# main-board.net
KiCad netlist of a schematic drawn in EAGLE
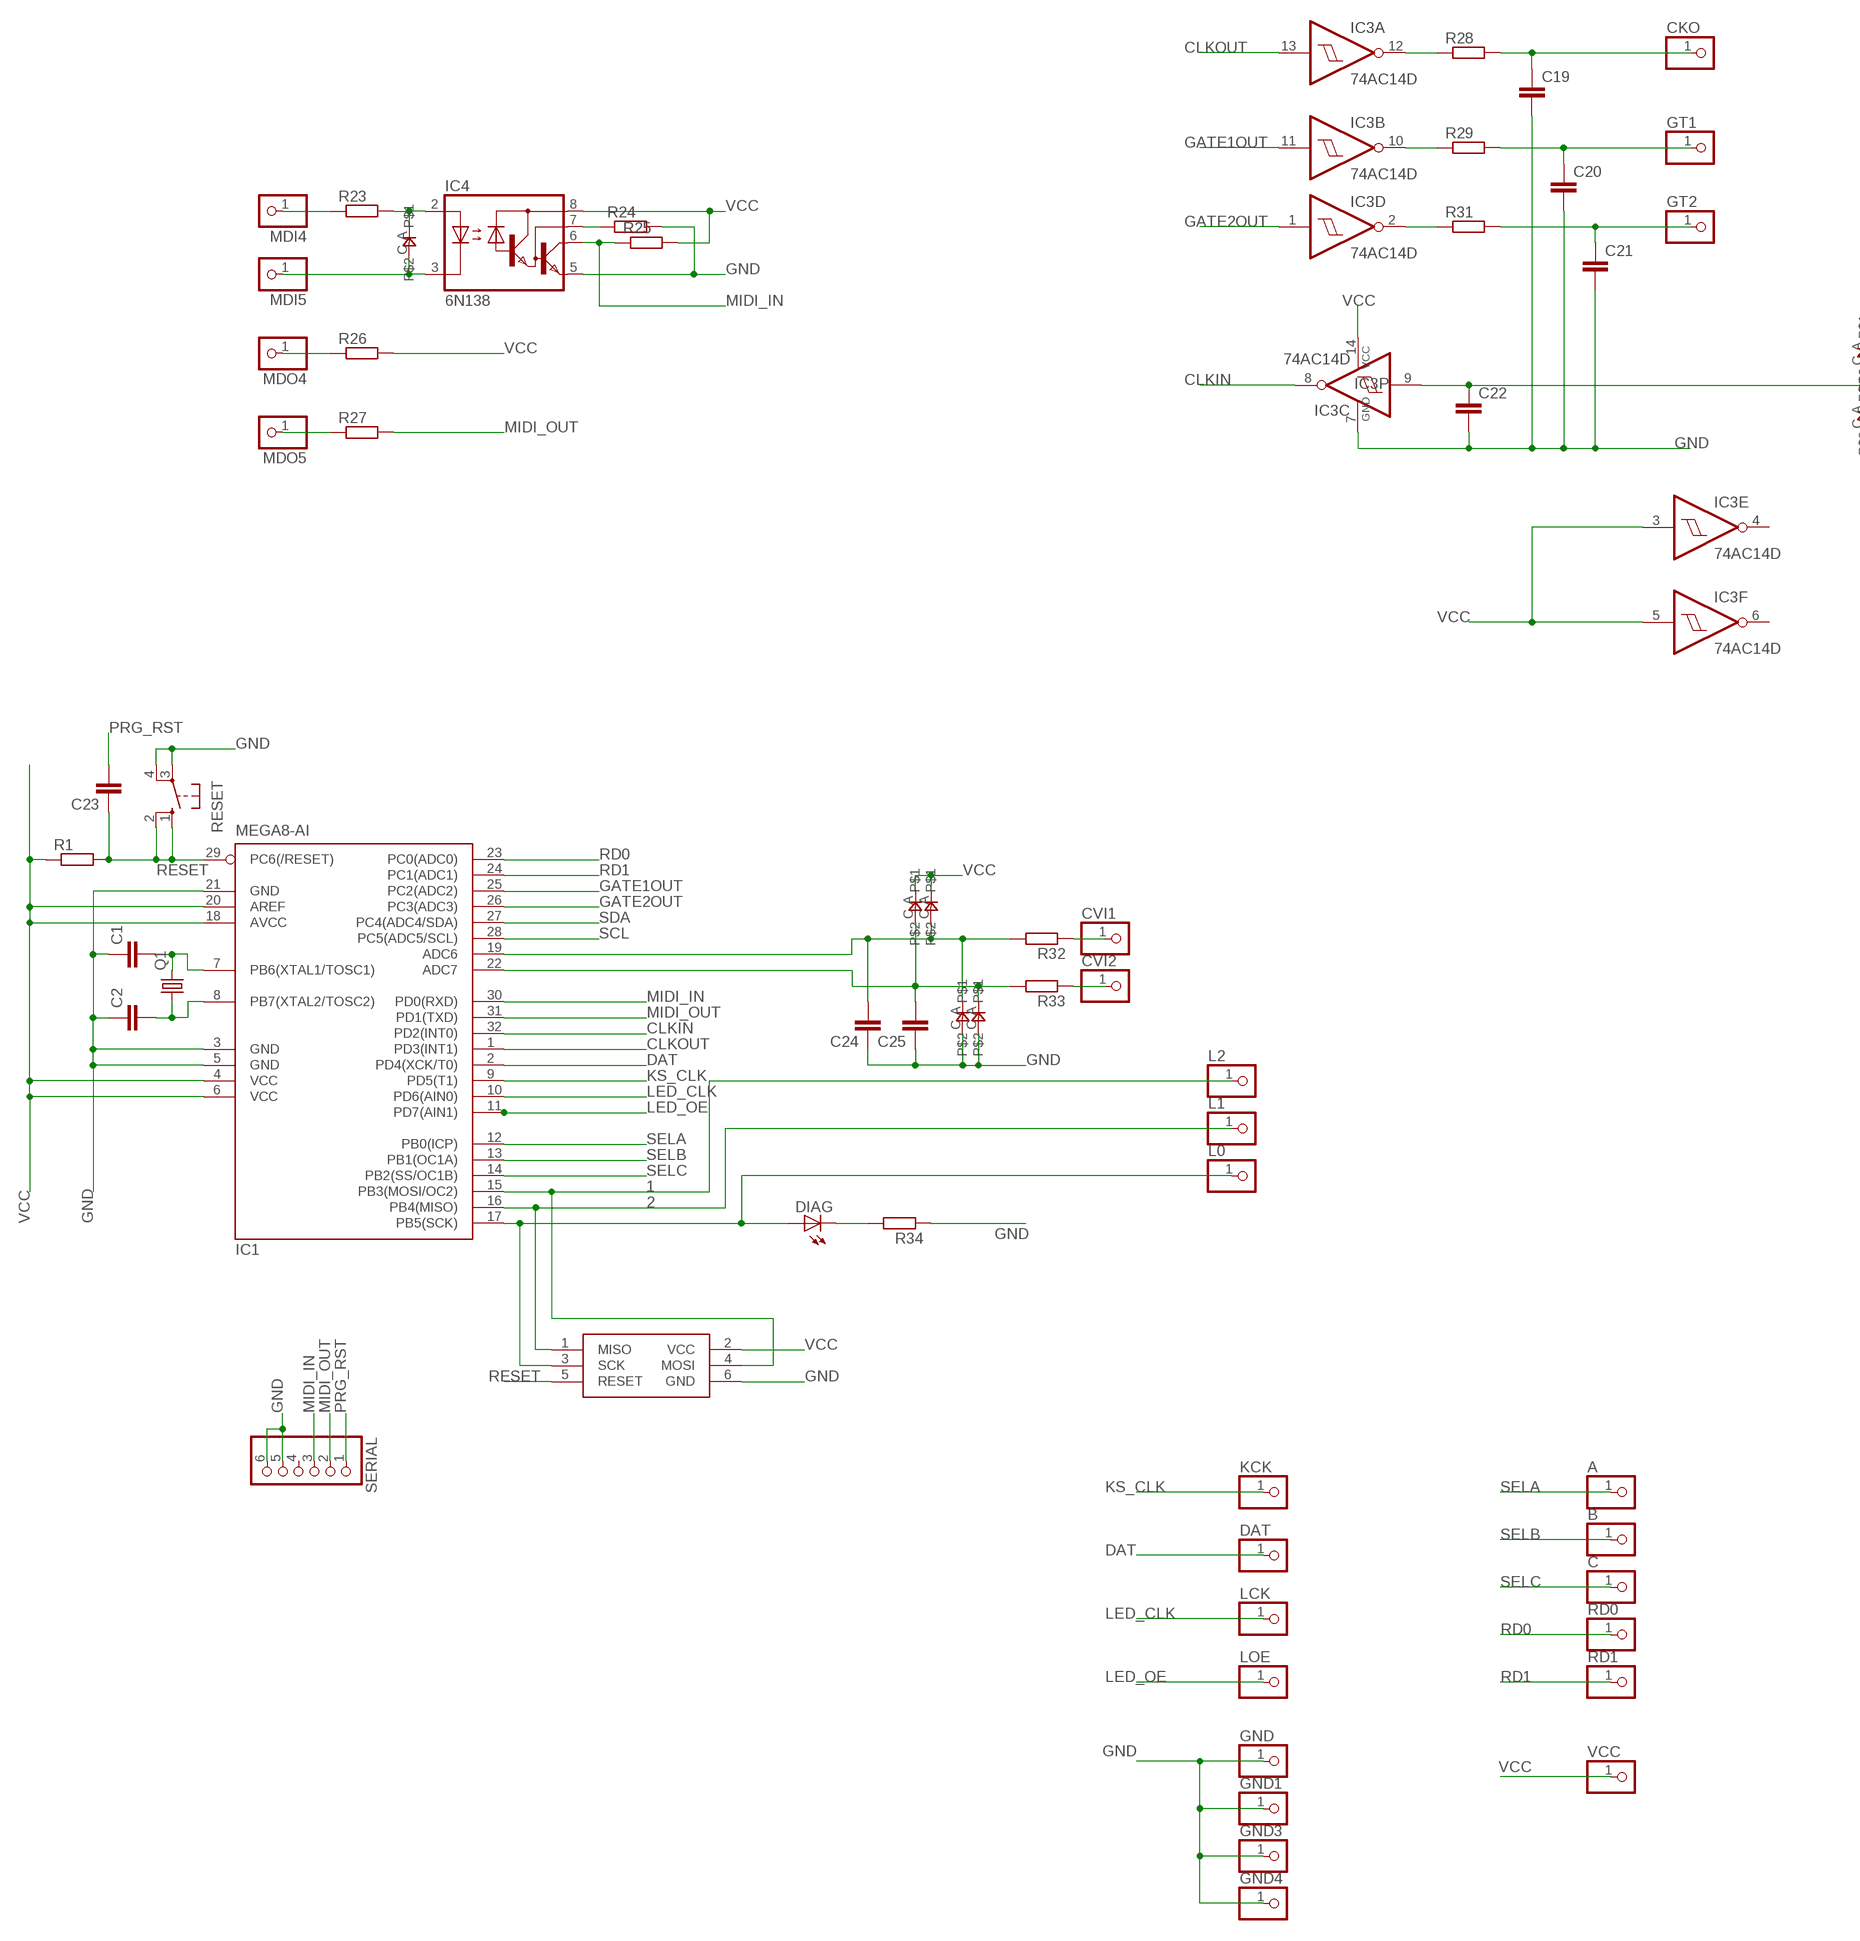
[diagram p0: schematic, sheet 1, part 1 of 2]
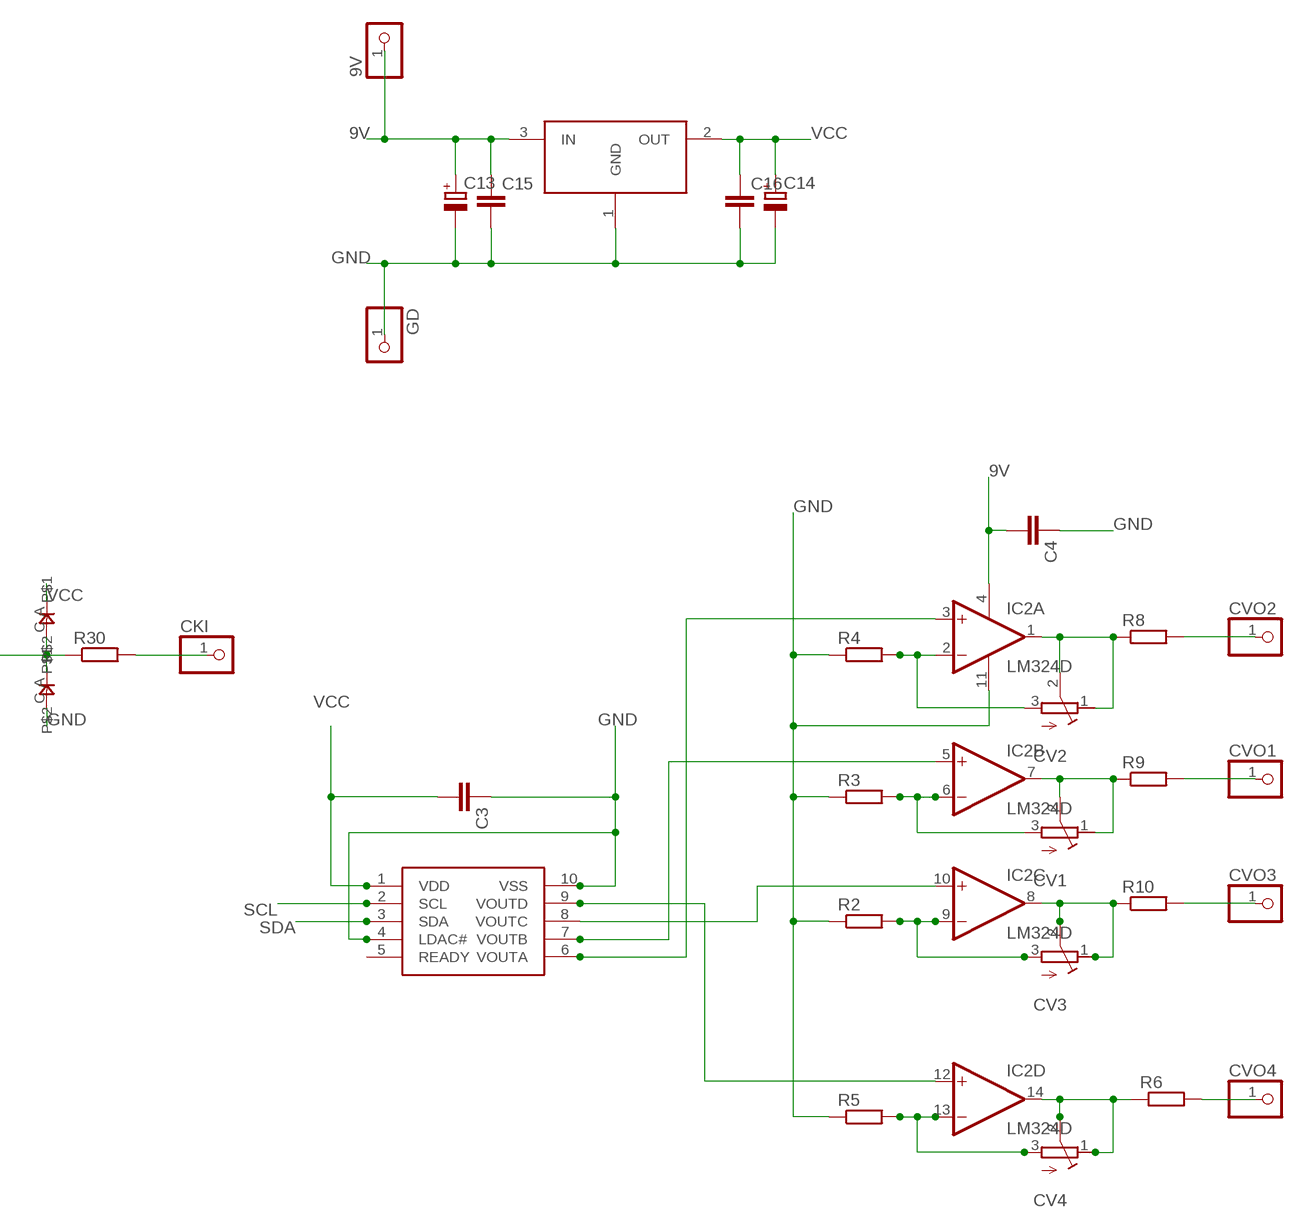
[diagram p1: schematic, sheet 1, part 2 of 2]

(export (version "E")
  (design (tool "Eeschema 10.0.6"))
  (components
    (comp (ref "9V")
      (value "PINHD-1X1")
      (footprint "eagle-import:1X01")
      (libsource (lib "eagle-import") (part "PINHD-1X1"))
    )
    (comp (ref "A")
      (value "PINHD-1X1")
      (footprint "eagle-import:1X01")
      (libsource (lib "eagle-import") (part "PINHD-1X1"))
    )
    (comp (ref "B")
      (value "PINHD-1X1")
      (footprint "eagle-import:1X01")
      (libsource (lib "eagle-import") (part "PINHD-1X1"))
    )
    (comp (ref "C")
      (value "PINHD-1X1")
      (footprint "eagle-import:1X01")
      (libsource (lib "eagle-import") (part "PINHD-1X1"))
    )
    (comp (ref "C1")
      (value "C-EUC0805")
      (footprint "eagle-import:C0805")
      (libsource (lib "eagle-import") (part "C-EUC0805"))
    )
    (comp (ref "C2")
      (value "C-EUC0805")
      (footprint "eagle-import:C0805")
      (libsource (lib "eagle-import") (part "C-EUC0805"))
    )
    (comp (ref "C3")
      (value "C-EUC0805")
      (footprint "eagle-import:C0805")
      (libsource (lib "eagle-import") (part "C-EUC0805"))
    )
    (comp (ref "C4")
      (value "C-EUC0805")
      (footprint "eagle-import:C0805")
      (libsource (lib "eagle-import") (part "C-EUC0805"))
    )
    (comp (ref "C13")
      (value "CPOL-EUE2-5")
      (footprint "eagle-import:E2-5")
      (libsource (lib "eagle-import") (part "CPOL-EUE2-5"))
    )
    (comp (ref "C14")
      (value "CPOL-EUE2-5")
      (footprint "eagle-import:E2-5")
      (libsource (lib "eagle-import") (part "CPOL-EUE2-5"))
    )
    (comp (ref "C15")
      (value "C-EUC0805")
      (footprint "eagle-import:C0805")
      (libsource (lib "eagle-import") (part "C-EUC0805"))
    )
    (comp (ref "C16")
      (value "C-EUC0805")
      (footprint "eagle-import:C0805")
      (libsource (lib "eagle-import") (part "C-EUC0805"))
    )
    (comp (ref "C19")
      (value "C-EUC0805")
      (footprint "eagle-import:C0805")
      (libsource (lib "eagle-import") (part "C-EUC0805"))
    )
    (comp (ref "C20")
      (value "C-EUC0805")
      (footprint "eagle-import:C0805")
      (libsource (lib "eagle-import") (part "C-EUC0805"))
    )
    (comp (ref "C21")
      (value "C-EUC0805")
      (footprint "eagle-import:C0805")
      (libsource (lib "eagle-import") (part "C-EUC0805"))
    )
    (comp (ref "C22")
      (value "C-EUC0805")
      (footprint "eagle-import:C0805")
      (libsource (lib "eagle-import") (part "C-EUC0805"))
    )
    (comp (ref "C23")
      (value "C-EUC0805")
      (footprint "eagle-import:C0805")
      (libsource (lib "eagle-import") (part "C-EUC0805"))
    )
    (comp (ref "C24")
      (value "C-EUC0805")
      (footprint "eagle-import:C0805")
      (libsource (lib "eagle-import") (part "C-EUC0805"))
    )
    (comp (ref "C25")
      (value "C-EUC0805")
      (footprint "eagle-import:C0805")
      (libsource (lib "eagle-import") (part "C-EUC0805"))
    )
    (comp (ref "CKI")
      (value "PINHD-1X1")
      (footprint "eagle-import:1X01")
      (libsource (lib "eagle-import") (part "PINHD-1X1"))
    )
    (comp (ref "CKO")
      (value "PINHD-1X1")
      (footprint "eagle-import:1X01")
      (libsource (lib "eagle-import") (part "PINHD-1X1"))
    )
    (comp (ref "CV1")
      (value "R-TRIMM3006P")
      (footprint "eagle-import:RTRIM3006P")
      (libsource (lib "eagle-import") (part "R-TRIMM3006P"))
    )
    (comp (ref "CV2")
      (value "R-TRIMM3006P")
      (footprint "eagle-import:RTRIM3006P")
      (libsource (lib "eagle-import") (part "R-TRIMM3006P"))
    )
    (comp (ref "CV3")
      (value "R-TRIMM3006P")
      (footprint "eagle-import:RTRIM3006P")
      (libsource (lib "eagle-import") (part "R-TRIMM3006P"))
    )
    (comp (ref "CV4")
      (value "R-TRIMM3006P")
      (footprint "eagle-import:RTRIM3006P")
      (libsource (lib "eagle-import") (part "R-TRIMM3006P"))
    )
    (comp (ref "CVI1")
      (value "PINHD-1X1")
      (footprint "eagle-import:1X01")
      (libsource (lib "eagle-import") (part "PINHD-1X1"))
    )
    (comp (ref "CVI2")
      (value "PINHD-1X1")
      (footprint "eagle-import:1X01")
      (libsource (lib "eagle-import") (part "PINHD-1X1"))
    )
    (comp (ref "CVO1")
      (value "PINHD-1X1")
      (footprint "eagle-import:1X01")
      (libsource (lib "eagle-import") (part "PINHD-1X1"))
    )
    (comp (ref "CVO2")
      (value "PINHD-1X1")
      (footprint "eagle-import:1X01")
      (libsource (lib "eagle-import") (part "PINHD-1X1"))
    )
    (comp (ref "CVO3")
      (value "PINHD-1X1")
      (footprint "eagle-import:1X01")
      (libsource (lib "eagle-import") (part "PINHD-1X1"))
    )
    (comp (ref "CVO4")
      (value "PINHD-1X1")
      (footprint "eagle-import:1X01")
      (libsource (lib "eagle-import") (part "PINHD-1X1"))
    )
    (comp (ref "D1")
      (value "0805DIODE")
      (footprint "eagle-import:0805DIODE")
      (libsource (lib "eagle-import") (part "0805DIODE"))
    )
    (comp (ref "D2")
      (value "0805DIODE")
      (footprint "eagle-import:0805DIODE")
      (libsource (lib "eagle-import") (part "0805DIODE"))
    )
    (comp (ref "D3")
      (value "0805DIODE")
      (footprint "eagle-import:0805DIODE")
      (libsource (lib "eagle-import") (part "0805DIODE"))
    )
    (comp (ref "D4")
      (value "0805DIODE")
      (footprint "eagle-import:0805DIODE")
      (libsource (lib "eagle-import") (part "0805DIODE"))
    )
    (comp (ref "D5")
      (value "0805DIODE")
      (footprint "eagle-import:0805DIODE")
      (libsource (lib "eagle-import") (part "0805DIODE"))
    )
    (comp (ref "D6")
      (value "0805DIODE")
      (footprint "eagle-import:0805DIODE")
      (libsource (lib "eagle-import") (part "0805DIODE"))
    )
    (comp (ref "D7")
      (value "0805DIODE")
      (footprint "eagle-import:0805DIODE")
      (libsource (lib "eagle-import") (part "0805DIODE"))
    )
    (comp (ref "DAT")
      (value "PINHD-1X1")
      (footprint "eagle-import:1X01")
      (libsource (lib "eagle-import") (part "PINHD-1X1"))
    )
    (comp (ref "DIAG")
      (value "LED3MM")
      (footprint "eagle-import:LED3MM")
      (libsource (lib "eagle-import") (part "LED3MM"))
    )
    (comp (ref "GD")
      (value "PINHD-1X1")
      (footprint "eagle-import:1X01")
      (libsource (lib "eagle-import") (part "PINHD-1X1"))
    )
    (comp (ref "GND")
      (value "PINHD-1X1")
      (footprint "eagle-import:1X01")
      (libsource (lib "eagle-import") (part "PINHD-1X1"))
    )
    (comp (ref "GND1")
      (value "PINHD-1X1")
      (footprint "eagle-import:1X01")
      (libsource (lib "eagle-import") (part "PINHD-1X1"))
    )
    (comp (ref "GND3")
      (value "PINHD-1X1")
      (footprint "eagle-import:1X01")
      (libsource (lib "eagle-import") (part "PINHD-1X1"))
    )
    (comp (ref "GND4")
      (value "PINHD-1X1")
      (footprint "eagle-import:1X01")
      (libsource (lib "eagle-import") (part "PINHD-1X1"))
    )
    (comp (ref "GT1")
      (value "PINHD-1X1")
      (footprint "eagle-import:1X01")
      (libsource (lib "eagle-import") (part "PINHD-1X1"))
    )
    (comp (ref "GT2")
      (value "PINHD-1X1")
      (footprint "eagle-import:1X01")
      (libsource (lib "eagle-import") (part "PINHD-1X1"))
    )
    (comp (ref "IC1")
      (value "MEGA8-AI")
      (footprint "eagle-import:TQFP32-08")
      (fields (field (name "MPN") "ATMEGA8-16AU"))
      (libsource (lib "eagle-import") (part "MEGA8-AI"))
    )
    (comp (ref "IC2")
      (value "LM324D")
      (footprint "eagle-import:SO14")
      (libsource (lib "eagle-import") (part "LM324D"))
    )
    (comp (ref "IC3")
      (value "74AC14D")
      (footprint "eagle-import:SO14")
      (libsource (lib "eagle-import") (part "7414DAC"))
    )
    (comp (ref "IC4")
      (value "6N138")
      (footprint "eagle-import:DIL08")
      (fields (field (name "MF") "VISHAY/TELEFUNKEN"))
      (libsource (lib "eagle-import") (part "6N138"))
    )
    (comp (ref "IC5")
      (value "MCP4728_QUAD_DAC")
      (footprint "eagle-import:MSOP10")
      (libsource (lib "eagle-import") (part "MCP4728_QUAD_DAC"))
    )
    (comp (ref "ICSP")
      (value "TAG_CONN_AVR")
      (footprint "eagle-import:TC2030-MCP-NL")
      (libsource (lib "eagle-import") (part "TAG_CONN_AVR"))
    )
    (comp (ref "KCK")
      (value "PINHD-1X1")
      (footprint "eagle-import:1X01")
      (libsource (lib "eagle-import") (part "PINHD-1X1"))
    )
    (comp (ref "L0")
      (value "PINHD-1X1")
      (footprint "eagle-import:1X01")
      (libsource (lib "eagle-import") (part "PINHD-1X1"))
    )
    (comp (ref "L1")
      (value "PINHD-1X1")
      (footprint "eagle-import:1X01")
      (libsource (lib "eagle-import") (part "PINHD-1X1"))
    )
    (comp (ref "L2")
      (value "PINHD-1X1")
      (footprint "eagle-import:1X01")
      (libsource (lib "eagle-import") (part "PINHD-1X1"))
    )
    (comp (ref "LCK")
      (value "PINHD-1X1")
      (footprint "eagle-import:1X01")
      (libsource (lib "eagle-import") (part "PINHD-1X1"))
    )
    (comp (ref "LOE")
      (value "PINHD-1X1")
      (footprint "eagle-import:1X01")
      (libsource (lib "eagle-import") (part "PINHD-1X1"))
    )
    (comp (ref "MDI4")
      (value "PINHD-1X1")
      (footprint "eagle-import:1X01")
      (libsource (lib "eagle-import") (part "PINHD-1X1"))
    )
    (comp (ref "MDI5")
      (value "PINHD-1X1")
      (footprint "eagle-import:1X01")
      (libsource (lib "eagle-import") (part "PINHD-1X1"))
    )
    (comp (ref "MDO4")
      (value "PINHD-1X1")
      (footprint "eagle-import:1X01")
      (libsource (lib "eagle-import") (part "PINHD-1X1"))
    )
    (comp (ref "MDO5")
      (value "PINHD-1X1")
      (footprint "eagle-import:1X01")
      (libsource (lib "eagle-import") (part "PINHD-1X1"))
    )
    (comp (ref "Q1")
      (value "CRYSTALHC49S")
      (footprint "eagle-import:HC49_S")
      (libsource (lib "eagle-import") (part "CRYSTALHC49S"))
    )
    (comp (ref "R1")
      (value "R-EU_R0805")
      (footprint "eagle-import:R0805")
      (libsource (lib "eagle-import") (part "R-EU_R0805"))
    )
    (comp (ref "R2")
      (value "R-EU_R0805")
      (footprint "eagle-import:R0805")
      (libsource (lib "eagle-import") (part "R-EU_R0805"))
    )
    (comp (ref "R3")
      (value "R-EU_R0805")
      (footprint "eagle-import:R0805")
      (libsource (lib "eagle-import") (part "R-EU_R0805"))
    )
    (comp (ref "R4")
      (value "R-EU_R0805")
      (footprint "eagle-import:R0805")
      (libsource (lib "eagle-import") (part "R-EU_R0805"))
    )
    (comp (ref "R5")
      (value "R-EU_R0805")
      (footprint "eagle-import:R0805")
      (libsource (lib "eagle-import") (part "R-EU_R0805"))
    )
    (comp (ref "R6")
      (value "R-EU_R0805")
      (footprint "eagle-import:R0805")
      (libsource (lib "eagle-import") (part "R-EU_R0805"))
    )
    (comp (ref "R8")
      (value "R-EU_R0805")
      (footprint "eagle-import:R0805")
      (libsource (lib "eagle-import") (part "R-EU_R0805"))
    )
    (comp (ref "R9")
      (value "R-EU_R0805")
      (footprint "eagle-import:R0805")
      (libsource (lib "eagle-import") (part "R-EU_R0805"))
    )
    (comp (ref "R10")
      (value "R-EU_R0805")
      (footprint "eagle-import:R0805")
      (libsource (lib "eagle-import") (part "R-EU_R0805"))
    )
    (comp (ref "R23")
      (value "R-EU_R0805")
      (footprint "eagle-import:R0805")
      (libsource (lib "eagle-import") (part "R-EU_R0805"))
    )
    (comp (ref "R24")
      (value "R-EU_R0805")
      (footprint "eagle-import:R0805")
      (libsource (lib "eagle-import") (part "R-EU_R0805"))
    )
    (comp (ref "R25")
      (value "R-EU_R0805")
      (footprint "eagle-import:R0805")
      (libsource (lib "eagle-import") (part "R-EU_R0805"))
    )
    (comp (ref "R26")
      (value "R-EU_R0805")
      (footprint "eagle-import:R0805")
      (libsource (lib "eagle-import") (part "R-EU_R0805"))
    )
    (comp (ref "R27")
      (value "R-EU_R0805")
      (footprint "eagle-import:R0805")
      (libsource (lib "eagle-import") (part "R-EU_R0805"))
    )
    (comp (ref "R28")
      (value "R-EU_R0805")
      (footprint "eagle-import:R0805")
      (libsource (lib "eagle-import") (part "R-EU_R0805"))
    )
    (comp (ref "R29")
      (value "R-EU_R0805")
      (footprint "eagle-import:R0805")
      (libsource (lib "eagle-import") (part "R-EU_R0805"))
    )
    (comp (ref "R30")
      (value "R-EU_R0805")
      (footprint "eagle-import:R0805")
      (libsource (lib "eagle-import") (part "R-EU_R0805"))
    )
    (comp (ref "R31")
      (value "R-EU_R0805")
      (footprint "eagle-import:R0805")
      (libsource (lib "eagle-import") (part "R-EU_R0805"))
    )
    (comp (ref "R32")
      (value "R-EU_R0805")
      (footprint "eagle-import:R0805")
      (libsource (lib "eagle-import") (part "R-EU_R0805"))
    )
    (comp (ref "R33")
      (value "R-EU_R0805")
      (footprint "eagle-import:R0805")
      (libsource (lib "eagle-import") (part "R-EU_R0805"))
    )
    (comp (ref "R34")
      (value "R-EU_R0805")
      (footprint "eagle-import:R0805")
      (libsource (lib "eagle-import") (part "R-EU_R0805"))
    )
    (comp (ref "RD0")
      (value "PINHD-1X1")
      (footprint "eagle-import:1X01")
      (libsource (lib "eagle-import") (part "PINHD-1X1"))
    )
    (comp (ref "RD1")
      (value "PINHD-1X1")
      (footprint "eagle-import:1X01")
      (libsource (lib "eagle-import") (part "PINHD-1X1"))
    )
    (comp (ref "REG1")
      (value "LD1086")
      (footprint "eagle-import:DPACK")
      (libsource (lib "eagle-import") (part "LD1086"))
    )
    (comp (ref "RESET")
      (value "10-XX")
      (footprint "eagle-import:B3F-10XX")
      (fields (field (name "MPN") "B3F-1000"))
      (libsource (lib "eagle-import") (part "10-XX"))
    )
    (comp (ref "SERIAL")
      (value "PINHD-1X6")
      (footprint "eagle-import:1X06")
      (libsource (lib "eagle-import") (part "PINHD-1X6"))
    )
    (comp (ref "VCC")
      (value "PINHD-1X1")
      (footprint "eagle-import:1X01")
      (libsource (lib "eagle-import") (part "PINHD-1X1"))
    )
  )
  (nets
    (net (code "1") (name "/1") (class "Default")
      (node (ref "IC1") (pin "15") (pinfunction "PB3(MOSI/OC2)_15") (pintype "bidirectional"))
      (node (ref "ICSP") (pin "4") (pinfunction "MOSI_4") (pintype "bidirectional"))
      (node (ref "L2") (pin "1") (pinfunction "1_1") (pintype "passive"))
    )
    (net (code "2") (name "/2") (class "Default")
      (node (ref "IC1") (pin "16") (pinfunction "PB4(MISO)_16") (pintype "bidirectional"))
      (node (ref "ICSP") (pin "1") (pinfunction "MISO_1") (pintype "bidirectional"))
      (node (ref "L1") (pin "1") (pinfunction "1_1") (pintype "passive"))
    )
    (net (code "3") (name "/9V") (class "Default")
      (node (ref "9V") (pin "1") (pinfunction "1_1") (pintype "passive"))
      (node (ref "C13") (pin "+") (pinfunction "+_+") (pintype "passive"))
      (node (ref "C15") (pin "1") (pinfunction "1_1") (pintype "passive"))
      (node (ref "C4") (pin "2") (pinfunction "2_2") (pintype "passive"))
      (node (ref "IC2") (pin "4") (pinfunction "V+_4") (pintype "power_in"))
      (node (ref "REG1") (pin "3") (pinfunction "IN_3") (pintype "bidirectional"))
    )
    (net (code "4") (name "/CLKIN") (class "Default")
      (node (ref "IC1") (pin "32") (pinfunction "PD2(INT0)_32") (pintype "bidirectional"))
      (node (ref "IC3") (pin "8") (pinfunction "O_8") (pintype "output"))
    )
    (net (code "5") (name "/CLKOUT") (class "Default")
      (node (ref "IC1") (pin "1") (pinfunction "PD3(INT1)_1") (pintype "bidirectional"))
      (node (ref "IC3") (pin "13") (pinfunction "I_13") (pintype "input"))
    )
    (net (code "6") (name "/DAT") (class "Default")
      (node (ref "DAT") (pin "1") (pinfunction "1_1") (pintype "passive"))
      (node (ref "IC1") (pin "2") (pinfunction "PD4(XCK/T0)_2") (pintype "bidirectional"))
    )
    (net (code "7") (name "/GATE1OUT") (class "Default")
      (node (ref "IC1") (pin "25") (pinfunction "PC2(ADC2)_25") (pintype "bidirectional"))
      (node (ref "IC3") (pin "11") (pinfunction "I_11") (pintype "input"))
    )
    (net (code "8") (name "/GATE2OUT") (class "Default")
      (node (ref "IC1") (pin "26") (pinfunction "PC3(ADC3)_26") (pintype "bidirectional"))
      (node (ref "IC3") (pin "1") (pinfunction "I_1") (pintype "input"))
    )
    (net (code "9") (name "/GND") (class "Default")
      (node (ref "C1") (pin "1") (pinfunction "1_1") (pintype "passive"))
      (node (ref "C13") (pin "-") (pinfunction "-_-") (pintype "passive"))
      (node (ref "C14") (pin "-") (pinfunction "-_-") (pintype "passive"))
      (node (ref "C15") (pin "2") (pinfunction "2_2") (pintype "passive"))
      (node (ref "C16") (pin "2") (pinfunction "2_2") (pintype "passive"))
      (node (ref "C19") (pin "2") (pinfunction "2_2") (pintype "passive"))
      (node (ref "C2") (pin "1") (pinfunction "1_1") (pintype "passive"))
      (node (ref "C20") (pin "2") (pinfunction "2_2") (pintype "passive"))
      (node (ref "C21") (pin "2") (pinfunction "2_2") (pintype "passive"))
      (node (ref "C22") (pin "2") (pinfunction "2_2") (pintype "passive"))
      (node (ref "C24") (pin "1") (pinfunction "1_1") (pintype "passive"))
      (node (ref "C25") (pin "1") (pinfunction "1_1") (pintype "passive"))
      (node (ref "C3") (pin "1") (pinfunction "1_1") (pintype "passive"))
      (node (ref "C4") (pin "1") (pinfunction "1_1") (pintype "passive"))
      (node (ref "D2") (pin "C") (pinfunction "P$1_C") (pintype "bidirectional"))
      (node (ref "D4") (pin "C") (pinfunction "P$1_C") (pintype "bidirectional"))
      (node (ref "D6") (pin "C") (pinfunction "P$1_C") (pintype "bidirectional"))
      (node (ref "GD") (pin "1") (pinfunction "1_1") (pintype "passive"))
      (node (ref "GND") (pin "1") (pinfunction "1_1") (pintype "passive"))
      (node (ref "GND1") (pin "1") (pinfunction "1_1") (pintype "passive"))
      (node (ref "GND3") (pin "1") (pinfunction "1_1") (pintype "passive"))
      (node (ref "GND4") (pin "1") (pinfunction "1_1") (pintype "passive"))
      (node (ref "IC1") (pin "21") (pinfunction "GND_21") (pintype "power_in"))
      (node (ref "IC1") (pin "3") (pinfunction "GND_3") (pintype "power_in"))
      (node (ref "IC1") (pin "5") (pinfunction "GND_5") (pintype "power_in"))
      (node (ref "IC2") (pin "11") (pinfunction "V-_11") (pintype "power_in"))
      (node (ref "IC3") (pin "7") (pinfunction "GND_7") (pintype "power_in"))
      (node (ref "IC4") (pin "5") (pinfunction "GND_5") (pintype "passive"))
      (node (ref "IC5") (pin "10") (pinfunction "VSS_10") (pintype "power_in"))
      (node (ref "IC5") (pin "4") (pinfunction "LDAC#_4") (pintype "bidirectional"))
      (node (ref "ICSP") (pin "6") (pinfunction "GND_6") (pintype "power_in"))
      (node (ref "R2") (pin "1") (pinfunction "1_1") (pintype "passive"))
      (node (ref "R24") (pin "2") (pinfunction "2_2") (pintype "passive"))
      (node (ref "R3") (pin "1") (pinfunction "1_1") (pintype "passive"))
      (node (ref "R34") (pin "1") (pinfunction "1_1") (pintype "passive"))
      (node (ref "R4") (pin "1") (pinfunction "1_1") (pintype "passive"))
      (node (ref "R5") (pin "1") (pinfunction "1_1") (pintype "passive"))
      (node (ref "REG1") (pin "1") (pinfunction "GND_1") (pintype "bidirectional"))
      (node (ref "RESET") (pin "3") (pinfunction "P_3") (pintype "passive"))
      (node (ref "RESET") (pin "4") (pinfunction "P1_4") (pintype "passive"))
      (node (ref "SERIAL") (pin "5") (pinfunction "5_5") (pintype "passive"))
      (node (ref "SERIAL") (pin "6") (pinfunction "6_6") (pintype "passive"))
    )
    (net (code "10") (name "/KS_CLK") (class "Default")
      (node (ref "IC1") (pin "9") (pinfunction "PD5(T1)_9") (pintype "bidirectional"))
      (node (ref "KCK") (pin "1") (pinfunction "1_1") (pintype "passive"))
    )
    (net (code "11") (name "/LED_CLK") (class "Default")
      (node (ref "IC1") (pin "10") (pinfunction "PD6(AIN0)_10") (pintype "bidirectional"))
      (node (ref "LCK") (pin "1") (pinfunction "1_1") (pintype "passive"))
    )
    (net (code "12") (name "/LED_OE") (class "Default")
      (node (ref "IC1") (pin "11") (pinfunction "PD7(AIN1)_11") (pintype "bidirectional"))
      (node (ref "LOE") (pin "1") (pinfunction "1_1") (pintype "passive"))
    )
    (net (code "13") (name "/MIDI_IN") (class "Default")
      (node (ref "IC1") (pin "30") (pinfunction "PD0(RXD)_30") (pintype "bidirectional"))
      (node (ref "IC4") (pin "6") (pinfunction "VO_6") (pintype "passive"))
      (node (ref "R25") (pin "1") (pinfunction "1_1") (pintype "passive"))
      (node (ref "SERIAL") (pin "3") (pinfunction "3_3") (pintype "passive"))
    )
    (net (code "14") (name "/MIDI_OUT") (class "Default")
      (node (ref "IC1") (pin "31") (pinfunction "PD1(TXD)_31") (pintype "bidirectional"))
      (node (ref "R27") (pin "2") (pinfunction "2_2") (pintype "passive"))
      (node (ref "SERIAL") (pin "2") (pinfunction "2_2") (pintype "passive"))
    )
    (net (code "15") (name "/PRG_RST") (class "Default")
      (node (ref "C23") (pin "2") (pinfunction "2_2") (pintype "passive"))
      (node (ref "SERIAL") (pin "1") (pinfunction "1_1") (pintype "passive"))
    )
    (net (code "16") (name "/RD0") (class "Default")
      (node (ref "IC1") (pin "23") (pinfunction "PC0(ADC0)_23") (pintype "bidirectional"))
      (node (ref "RD0") (pin "1") (pinfunction "1_1") (pintype "passive"))
    )
    (net (code "17") (name "/RD1") (class "Default")
      (node (ref "IC1") (pin "24") (pinfunction "PC1(ADC1)_24") (pintype "bidirectional"))
      (node (ref "RD1") (pin "1") (pinfunction "1_1") (pintype "passive"))
    )
    (net (code "18") (name "/RESET") (class "Default")
      (node (ref "C23") (pin "1") (pinfunction "1_1") (pintype "passive"))
      (node (ref "IC1") (pin "29") (pinfunction "PC6(/RESET)_29") (pintype "bidirectional"))
      (node (ref "ICSP") (pin "5") (pinfunction "RESET_5") (pintype "bidirectional"))
      (node (ref "R1") (pin "2") (pinfunction "2_2") (pintype "passive"))
      (node (ref "RESET") (pin "1") (pinfunction "S_1") (pintype "passive"))
      (node (ref "RESET") (pin "2") (pinfunction "S1_2") (pintype "passive"))
    )
    (net (code "19") (name "/SCL") (class "Default")
      (node (ref "IC1") (pin "28") (pinfunction "PC5(ADC5/SCL)_28") (pintype "bidirectional"))
      (node (ref "IC5") (pin "2") (pinfunction "SCL_2") (pintype "bidirectional"))
    )
    (net (code "20") (name "/SDA") (class "Default")
      (node (ref "IC1") (pin "27") (pinfunction "PC4(ADC4/SDA)_27") (pintype "bidirectional"))
      (node (ref "IC5") (pin "3") (pinfunction "SDA_3") (pintype "bidirectional"))
    )
    (net (code "21") (name "/SELA") (class "Default")
      (node (ref "A") (pin "1") (pinfunction "1_1") (pintype "passive"))
      (node (ref "IC1") (pin "12") (pinfunction "PB0(ICP)_12") (pintype "bidirectional"))
    )
    (net (code "22") (name "/SELB") (class "Default")
      (node (ref "B") (pin "1") (pinfunction "1_1") (pintype "passive"))
      (node (ref "IC1") (pin "13") (pinfunction "PB1(OC1A)_13") (pintype "bidirectional"))
    )
    (net (code "23") (name "/SELC") (class "Default")
      (node (ref "C") (pin "1") (pinfunction "1_1") (pintype "passive"))
      (node (ref "IC1") (pin "14") (pinfunction "PB2(SS/OC1B)_14") (pintype "bidirectional"))
    )
    (net (code "24") (name "/VCC") (class "Default")
      (node (ref "C14") (pin "+") (pinfunction "+_+") (pintype "passive"))
      (node (ref "C16") (pin "1") (pinfunction "1_1") (pintype "passive"))
      (node (ref "C3") (pin "2") (pinfunction "2_2") (pintype "passive"))
      (node (ref "D3") (pin "A") (pinfunction "P$2_A") (pintype "bidirectional"))
      (node (ref "D5") (pin "A") (pinfunction "P$2_A") (pintype "bidirectional"))
      (node (ref "D7") (pin "A") (pinfunction "P$2_A") (pintype "bidirectional"))
      (node (ref "IC1") (pin "18") (pinfunction "AVCC_18") (pintype "power_in"))
      (node (ref "IC1") (pin "20") (pinfunction "AREF_20") (pintype "passive"))
      (node (ref "IC1") (pin "4") (pinfunction "VCC_4") (pintype "power_in"))
      (node (ref "IC1") (pin "6") (pinfunction "VCC_6") (pintype "power_in"))
      (node (ref "IC3") (pin "14") (pinfunction "VCC_14") (pintype "power_in"))
      (node (ref "IC3") (pin "3") (pinfunction "I_3") (pintype "input"))
      (node (ref "IC3") (pin "5") (pinfunction "I_5") (pintype "input"))
      (node (ref "IC4") (pin "8") (pinfunction "VCC_8") (pintype "passive"))
      (node (ref "IC5") (pin "1") (pinfunction "VDD_1") (pintype "power_in"))
      (node (ref "ICSP") (pin "2") (pinfunction "VCC_2") (pintype "power_in"))
      (node (ref "R1") (pin "1") (pinfunction "1_1") (pintype "passive"))
      (node (ref "R25") (pin "2") (pinfunction "2_2") (pintype "passive"))
      (node (ref "R26") (pin "2") (pinfunction "2_2") (pintype "passive"))
      (node (ref "REG1") (pin "2") (pinfunction "OUT_2") (pintype "bidirectional"))
      (node (ref "VCC") (pin "1") (pinfunction "1_1") (pintype "passive"))
    )
    (net (code "25") (name "Net-(C19-Pad1)") (class "Default")
      (node (ref "C19") (pin "1") (pinfunction "1_1") (pintype "passive"))
      (node (ref "CKO") (pin "1") (pinfunction "1_1") (pintype "passive"))
      (node (ref "R28") (pin "2") (pinfunction "2_2") (pintype "passive"))
    )
    (net (code "26") (name "Net-(C20-Pad1)") (class "Default")
      (node (ref "C20") (pin "1") (pinfunction "1_1") (pintype "passive"))
      (node (ref "GT1") (pin "1") (pinfunction "1_1") (pintype "passive"))
      (node (ref "R29") (pin "2") (pinfunction "2_2") (pintype "passive"))
    )
    (net (code "27") (name "Net-(C21-Pad1)") (class "Default")
      (node (ref "C21") (pin "1") (pinfunction "1_1") (pintype "passive"))
      (node (ref "GT2") (pin "1") (pinfunction "1_1") (pintype "passive"))
      (node (ref "R31") (pin "2") (pinfunction "2_2") (pintype "passive"))
    )
    (net (code "28") (name "Net-(CKI-Pad1)") (class "Default")
      (node (ref "CKI") (pin "1") (pinfunction "1_1") (pintype "passive"))
      (node (ref "R30") (pin "2") (pinfunction "2_2") (pintype "passive"))
    )
    (net (code "29") (name "Net-(CV1-A)") (class "Default")
      (node (ref "CV1") (pin "1") (pinfunction "A_1") (pintype "passive"))
      (node (ref "CV1") (pin "2") (pinfunction "S_2") (pintype "passive"))
      (node (ref "IC2") (pin "7") (pinfunction "OUT_7") (pintype "output"))
      (node (ref "R9") (pin "1") (pinfunction "1_1") (pintype "passive"))
    )
    (net (code "30") (name "Net-(CV1-E)") (class "Default")
      (node (ref "CV1") (pin "3") (pinfunction "E_3") (pintype "passive"))
      (node (ref "IC2") (pin "6") (pinfunction "-IN_6") (pintype "input"))
      (node (ref "R3") (pin "2") (pinfunction "2_2") (pintype "passive"))
    )
    (net (code "31") (name "Net-(CV2-A)") (class "Default")
      (node (ref "CV2") (pin "1") (pinfunction "A_1") (pintype "passive"))
      (node (ref "CV2") (pin "2") (pinfunction "S_2") (pintype "passive"))
      (node (ref "IC2") (pin "1") (pinfunction "OUT_1") (pintype "output"))
      (node (ref "R8") (pin "1") (pinfunction "1_1") (pintype "passive"))
    )
    (net (code "32") (name "Net-(CV2-E)") (class "Default")
      (node (ref "CV2") (pin "3") (pinfunction "E_3") (pintype "passive"))
      (node (ref "IC2") (pin "2") (pinfunction "-IN_2") (pintype "input"))
      (node (ref "R4") (pin "2") (pinfunction "2_2") (pintype "passive"))
    )
    (net (code "33") (name "Net-(CV3-A)") (class "Default")
      (node (ref "CV3") (pin "1") (pinfunction "A_1") (pintype "passive"))
      (node (ref "CV3") (pin "2") (pinfunction "S_2") (pintype "passive"))
      (node (ref "IC2") (pin "8") (pinfunction "OUT_8") (pintype "output"))
      (node (ref "R10") (pin "1") (pinfunction "1_1") (pintype "passive"))
    )
    (net (code "34") (name "Net-(CV3-E)") (class "Default")
      (node (ref "CV3") (pin "3") (pinfunction "E_3") (pintype "passive"))
      (node (ref "IC2") (pin "9") (pinfunction "-IN_9") (pintype "input"))
      (node (ref "R2") (pin "2") (pinfunction "2_2") (pintype "passive"))
    )
    (net (code "35") (name "Net-(CV4-A)") (class "Default")
      (node (ref "CV4") (pin "1") (pinfunction "A_1") (pintype "passive"))
      (node (ref "CV4") (pin "2") (pinfunction "S_2") (pintype "passive"))
      (node (ref "IC2") (pin "14") (pinfunction "OUT_14") (pintype "output"))
      (node (ref "R6") (pin "1") (pinfunction "1_1") (pintype "passive"))
    )
    (net (code "36") (name "Net-(CV4-E)") (class "Default")
      (node (ref "CV4") (pin "3") (pinfunction "E_3") (pintype "passive"))
      (node (ref "IC2") (pin "13") (pinfunction "-IN_13") (pintype "input"))
      (node (ref "R5") (pin "2") (pinfunction "2_2") (pintype "passive"))
    )
    (net (code "37") (name "Net-(CVI1-Pad1)") (class "Default")
      (node (ref "CVI1") (pin "1") (pinfunction "1_1") (pintype "passive"))
      (node (ref "R32") (pin "1") (pinfunction "1_1") (pintype "passive"))
    )
    (net (code "38") (name "Net-(CVI2-Pad1)") (class "Default")
      (node (ref "CVI2") (pin "1") (pinfunction "1_1") (pintype "passive"))
      (node (ref "R33") (pin "1") (pinfunction "1_1") (pintype "passive"))
    )
    (net (code "39") (name "Net-(CVO1-Pad1)") (class "Default")
      (node (ref "CVO1") (pin "1") (pinfunction "1_1") (pintype "passive"))
      (node (ref "R9") (pin "2") (pinfunction "2_2") (pintype "passive"))
    )
    (net (code "40") (name "Net-(CVO2-Pad1)") (class "Default")
      (node (ref "CVO2") (pin "1") (pinfunction "1_1") (pintype "passive"))
      (node (ref "R8") (pin "2") (pinfunction "2_2") (pintype "passive"))
    )
    (net (code "41") (name "Net-(CVO3-Pad1)") (class "Default")
      (node (ref "CVO3") (pin "1") (pinfunction "1_1") (pintype "passive"))
      (node (ref "R10") (pin "2") (pinfunction "2_2") (pintype "passive"))
    )
    (net (code "42") (name "Net-(CVO4-Pad1)") (class "Default")
      (node (ref "CVO4") (pin "1") (pinfunction "1_1") (pintype "passive"))
      (node (ref "R6") (pin "2") (pinfunction "2_2") (pintype "passive"))
    )
    (net (code "43") (name "Net-(D1-P$1)") (class "Default")
      (node (ref "D1") (pin "C") (pinfunction "P$1_C") (pintype "bidirectional"))
      (node (ref "IC4") (pin "3") (pinfunction "C_3") (pintype "passive"))
      (node (ref "MDI5") (pin "1") (pinfunction "1_1") (pintype "passive"))
    )
    (net (code "44") (name "Net-(D1-P$2)") (class "Default")
      (node (ref "D1") (pin "A") (pinfunction "P$2_A") (pintype "bidirectional"))
      (node (ref "IC4") (pin "2") (pinfunction "A_2") (pintype "passive"))
      (node (ref "R23") (pin "2") (pinfunction "2_2") (pintype "passive"))
    )
    (net (code "45") (name "Net-(D2-P$2)") (class "Default")
      (node (ref "C24") (pin "2") (pinfunction "2_2") (pintype "passive"))
      (node (ref "D2") (pin "A") (pinfunction "P$2_A") (pintype "bidirectional"))
      (node (ref "D3") (pin "C") (pinfunction "P$1_C") (pintype "bidirectional"))
      (node (ref "IC1") (pin "19") (pinfunction "ADC6_19") (pintype "bidirectional"))
      (node (ref "R32") (pin "2") (pinfunction "2_2") (pintype "passive"))
    )
    (net (code "46") (name "Net-(D4-P$2)") (class "Default")
      (node (ref "C25") (pin "2") (pinfunction "2_2") (pintype "passive"))
      (node (ref "D4") (pin "A") (pinfunction "P$2_A") (pintype "bidirectional"))
      (node (ref "D5") (pin "C") (pinfunction "P$1_C") (pintype "bidirectional"))
      (node (ref "IC1") (pin "22") (pinfunction "ADC7_22") (pintype "bidirectional"))
      (node (ref "R33") (pin "2") (pinfunction "2_2") (pintype "passive"))
    )
    (net (code "47") (name "Net-(D6-P$2)") (class "Default")
      (node (ref "C22") (pin "1") (pinfunction "1_1") (pintype "passive"))
      (node (ref "D6") (pin "A") (pinfunction "P$2_A") (pintype "bidirectional"))
      (node (ref "D7") (pin "C") (pinfunction "P$1_C") (pintype "bidirectional"))
      (node (ref "IC3") (pin "9") (pinfunction "I_9") (pintype "input"))
      (node (ref "R30") (pin "1") (pinfunction "1_1") (pintype "passive"))
    )
    (net (code "48") (name "Net-(DIAG-C)") (class "Default")
      (node (ref "DIAG") (pin "K") (pinfunction "C_K") (pintype "passive"))
      (node (ref "R34") (pin "2") (pinfunction "2_2") (pintype "passive"))
    )
    (net (code "49") (name "Net-(IC1-PB5(SCK))") (class "Default")
      (node (ref "DIAG") (pin "A") (pinfunction "A_A") (pintype "passive"))
      (node (ref "IC1") (pin "17") (pinfunction "PB5(SCK)_17") (pintype "bidirectional"))
      (node (ref "ICSP") (pin "3") (pinfunction "SCK_3") (pintype "bidirectional"))
      (node (ref "L0") (pin "1") (pinfunction "1_1") (pintype "passive"))
    )
    (net (code "50") (name "Net-(IC1-PB6(XTAL1{slash}TOSC1))") (class "Default")
      (node (ref "C1") (pin "2") (pinfunction "2_2") (pintype "passive"))
      (node (ref "IC1") (pin "7") (pinfunction "PB6(XTAL1/TOSC1)_7") (pintype "bidirectional"))
      (node (ref "Q1") (pin "2") (pinfunction "2_2") (pintype "passive"))
    )
    (net (code "51") (name "Net-(IC1-PB7(XTAL2{slash}TOSC2))") (class "Default")
      (node (ref "C2") (pin "2") (pinfunction "2_2") (pintype "passive"))
      (node (ref "IC1") (pin "8") (pinfunction "PB7(XTAL2/TOSC2)_8") (pintype "bidirectional"))
      (node (ref "Q1") (pin "1") (pinfunction "1_1") (pintype "passive"))
    )
    (net (code "52") (name "Net-(IC2A-+IN)") (class "Default")
      (node (ref "IC2") (pin "3") (pinfunction "+IN_3") (pintype "input"))
      (node (ref "IC5") (pin "6") (pinfunction "VOUTA_6") (pintype "bidirectional"))
    )
    (net (code "53") (name "Net-(IC2B-+IN)") (class "Default")
      (node (ref "IC2") (pin "5") (pinfunction "+IN_5") (pintype "input"))
      (node (ref "IC5") (pin "7") (pinfunction "VOUTB_7") (pintype "bidirectional"))
    )
    (net (code "54") (name "Net-(IC2C-+IN)") (class "Default")
      (node (ref "IC2") (pin "10") (pinfunction "+IN_10") (pintype "input"))
      (node (ref "IC5") (pin "8") (pinfunction "VOUTC_8") (pintype "bidirectional"))
    )
    (net (code "55") (name "Net-(IC2D-+IN)") (class "Default")
      (node (ref "IC2") (pin "12") (pinfunction "+IN_12") (pintype "input"))
      (node (ref "IC5") (pin "9") (pinfunction "VOUTD_9") (pintype "bidirectional"))
    )
    (net (code "56") (name "Net-(IC3A-O)") (class "Default")
      (node (ref "IC3") (pin "12") (pinfunction "O_12") (pintype "output"))
      (node (ref "R28") (pin "1") (pinfunction "1_1") (pintype "passive"))
    )
    (net (code "57") (name "Net-(IC3B-O)") (class "Default")
      (node (ref "IC3") (pin "10") (pinfunction "O_10") (pintype "output"))
      (node (ref "R29") (pin "1") (pinfunction "1_1") (pintype "passive"))
    )
    (net (code "58") (name "Net-(IC3D-O)") (class "Default")
      (node (ref "IC3") (pin "2") (pinfunction "O_2") (pintype "output"))
      (node (ref "R31") (pin "1") (pinfunction "1_1") (pintype "passive"))
    )
    (net (code "59") (name "Net-(IC4-VB)") (class "Default")
      (node (ref "IC4") (pin "7") (pinfunction "VB_7") (pintype "passive"))
      (node (ref "R24") (pin "1") (pinfunction "1_1") (pintype "passive"))
    )
    (net (code "60") (name "Net-(MDI4-Pad1)") (class "Default")
      (node (ref "MDI4") (pin "1") (pinfunction "1_1") (pintype "passive"))
      (node (ref "R23") (pin "1") (pinfunction "1_1") (pintype "passive"))
    )
    (net (code "61") (name "Net-(MDO4-Pad1)") (class "Default")
      (node (ref "MDO4") (pin "1") (pinfunction "1_1") (pintype "passive"))
      (node (ref "R26") (pin "1") (pinfunction "1_1") (pintype "passive"))
    )
    (net (code "62") (name "Net-(MDO5-Pad1)") (class "Default")
      (node (ref "MDO5") (pin "1") (pinfunction "1_1") (pintype "passive"))
      (node (ref "R27") (pin "1") (pinfunction "1_1") (pintype "passive"))
    )
    (net (code "63") (name "unconnected-(IC3E-O-Pad4)") (class "Default")
      (node (ref "IC3") (pin "4") (pinfunction "O_4") (pintype "output"))
    )
    (net (code "64") (name "unconnected-(IC3F-O-Pad6)") (class "Default")
      (node (ref "IC3") (pin "6") (pinfunction "O_6") (pintype "output"))
    )
    (net (code "65") (name "unconnected-(IC5-READY-Pad5)") (class "Default")
      (node (ref "IC5") (pin "5") (pinfunction "READY_5") (pintype "bidirectional"))
    )
    (net (code "66") (name "unconnected-(SERIAL-Pad4)") (class "Default")
      (node (ref "SERIAL") (pin "4") (pinfunction "4_4") (pintype "passive"))
    )
  )
)
